# PicTouchTest.net
KiCad netlist of a schematic drawn in EAGLE
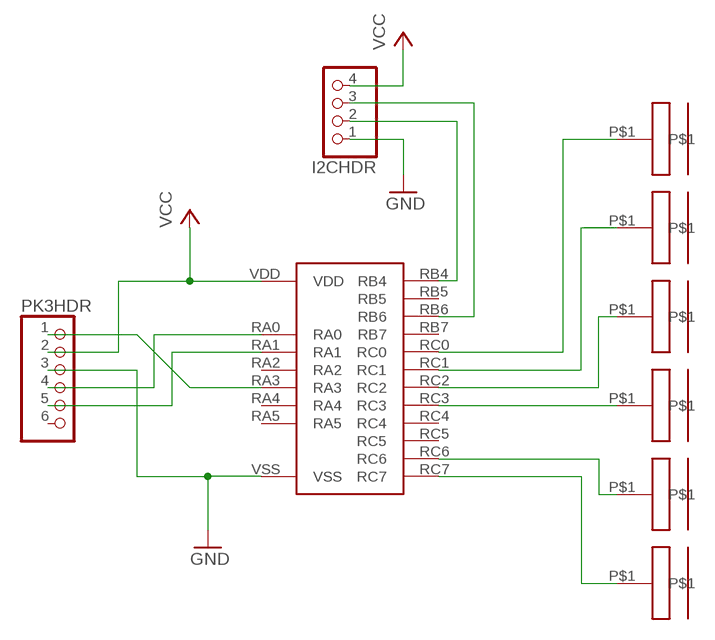
[diagram p0: schematic, sheet 1]

(export (version "E")
  (design (tool "Eeschema 10.0.6"))
  (components
    (comp (ref "I2CHDR")
      (value "PINHD-1X4")
      (footprint "eagle-import:1X04")
      (libsource (lib "eagle-import") (part "PINHD-1X4"))
    )
    (comp (ref "PK3HDR")
      (value "PINHD-1X6")
      (footprint "eagle-import:1X06")
      (libsource (lib "eagle-import") (part "PINHD-1X6"))
    )
    (comp (ref "U$1")
      (value "PIC16F1707")
      (footprint "eagle-import:PIC16F1707")
      (libsource (lib "eagle-import") (part "PIC16F1707"))
    )
    (comp (ref "U$2")
      (value "CAPTOUCH20MMRND")
      (footprint "eagle-import:20MMROUND")
      (libsource (lib "eagle-import") (part "CAPTOUCH20MMRND"))
    )
    (comp (ref "U$3")
      (value "CAPTOUCH20MMRND")
      (footprint "eagle-import:20MMROUND")
      (libsource (lib "eagle-import") (part "CAPTOUCH20MMRND"))
    )
    (comp (ref "U$4")
      (value "CAPTOUCH20MMRND")
      (footprint "eagle-import:20MMROUND")
      (libsource (lib "eagle-import") (part "CAPTOUCH20MMRND"))
    )
    (comp (ref "U$5")
      (value "CAPTOUCH20MMRND")
      (footprint "eagle-import:20MMROUND")
      (libsource (lib "eagle-import") (part "CAPTOUCH20MMRND"))
    )
    (comp (ref "U$6")
      (value "CAPTOUCH20MMRND")
      (footprint "eagle-import:20MMROUND")
      (libsource (lib "eagle-import") (part "CAPTOUCH20MMRND"))
    )
    (comp (ref "U$7")
      (value "CAPTOUCH20MMRND")
      (footprint "eagle-import:20MMROUND")
      (libsource (lib "eagle-import") (part "CAPTOUCH20MMRND"))
    )
  )
  (nets
    (net (code "1") (name "GND") (class "Default")
      (node (ref "I2CHDR") (pin "1") (pinfunction "1_1") (pintype "passive"))
      (node (ref "PK3HDR") (pin "3") (pinfunction "3_3") (pintype "passive"))
      (node (ref "U$1") (pin "VSS") (pinfunction "VSS_VSS") (pintype "bidirectional"))
    )
    (net (code "2") (name "Net-(I2CHDR-Pad2)") (class "Default")
      (node (ref "I2CHDR") (pin "2") (pinfunction "2_2") (pintype "passive"))
      (node (ref "U$1") (pin "RB4") (pinfunction "RB4_RB4") (pintype "bidirectional"))
    )
    (net (code "3") (name "Net-(I2CHDR-Pad3)") (class "Default")
      (node (ref "I2CHDR") (pin "3") (pinfunction "3_3") (pintype "passive"))
      (node (ref "U$1") (pin "RB6") (pinfunction "RB6_RB6") (pintype "bidirectional"))
    )
    (net (code "4") (name "Net-(PK3HDR-Pad1)") (class "Default")
      (node (ref "PK3HDR") (pin "1") (pinfunction "1_1") (pintype "passive"))
      (node (ref "U$1") (pin "RA3") (pinfunction "RA3_RA3") (pintype "bidirectional"))
    )
    (net (code "5") (name "Net-(PK3HDR-Pad4)") (class "Default")
      (node (ref "PK3HDR") (pin "4") (pinfunction "4_4") (pintype "passive"))
      (node (ref "U$1") (pin "RA0") (pinfunction "RA0_RA0") (pintype "bidirectional"))
    )
    (net (code "6") (name "Net-(PK3HDR-Pad5)") (class "Default")
      (node (ref "PK3HDR") (pin "5") (pinfunction "5_5") (pintype "passive"))
      (node (ref "U$1") (pin "RA1") (pinfunction "RA1_RA1") (pintype "bidirectional"))
    )
    (net (code "7") (name "Net-(U$1-PadRC0)") (class "Default")
      (node (ref "U$1") (pin "RC0") (pinfunction "RC0_RC0") (pintype "bidirectional"))
      (node (ref "U$2") (pin "P$1") (pinfunction "P$1_P$1") (pintype "bidirectional"))
    )
    (net (code "8") (name "Net-(U$1-PadRC1)") (class "Default")
      (node (ref "U$1") (pin "RC1") (pinfunction "RC1_RC1") (pintype "bidirectional"))
      (node (ref "U$3") (pin "P$1") (pinfunction "P$1_P$1") (pintype "bidirectional"))
    )
    (net (code "9") (name "Net-(U$1-PadRC2)") (class "Default")
      (node (ref "U$1") (pin "RC2") (pinfunction "RC2_RC2") (pintype "bidirectional"))
      (node (ref "U$4") (pin "P$1") (pinfunction "P$1_P$1") (pintype "bidirectional"))
    )
    (net (code "10") (name "Net-(U$1-PadRC3)") (class "Default")
      (node (ref "U$1") (pin "RC3") (pinfunction "RC3_RC3") (pintype "bidirectional"))
      (node (ref "U$5") (pin "P$1") (pinfunction "P$1_P$1") (pintype "bidirectional"))
    )
    (net (code "11") (name "Net-(U$1-PadRC6)") (class "Default")
      (node (ref "U$1") (pin "RC6") (pinfunction "RC6_RC6") (pintype "bidirectional"))
      (node (ref "U$6") (pin "P$1") (pinfunction "P$1_P$1") (pintype "bidirectional"))
    )
    (net (code "12") (name "Net-(U$1-PadRC7)") (class "Default")
      (node (ref "U$1") (pin "RC7") (pinfunction "RC7_RC7") (pintype "bidirectional"))
      (node (ref "U$7") (pin "P$1") (pinfunction "P$1_P$1") (pintype "bidirectional"))
    )
    (net (code "13") (name "VCC") (class "Default")
      (node (ref "I2CHDR") (pin "4") (pinfunction "4_4") (pintype "passive"))
      (node (ref "PK3HDR") (pin "2") (pinfunction "2_2") (pintype "passive"))
      (node (ref "U$1") (pin "VDD") (pinfunction "VDD_VDD") (pintype "bidirectional"))
    )
    (net (code "14") (name "unconnected-(PK3HDR-Pad6)") (class "Default")
      (node (ref "PK3HDR") (pin "6") (pinfunction "6_6") (pintype "passive"))
    )
    (net (code "15") (name "unconnected-(U$1-PadRA2)") (class "Default")
      (node (ref "U$1") (pin "RA2") (pinfunction "RA2_RA2") (pintype "bidirectional"))
    )
    (net (code "16") (name "unconnected-(U$1-PadRA4)") (class "Default")
      (node (ref "U$1") (pin "RA4") (pinfunction "RA4_RA4") (pintype "bidirectional"))
    )
    (net (code "17") (name "unconnected-(U$1-PadRA5)") (class "Default")
      (node (ref "U$1") (pin "RA5") (pinfunction "RA5_RA5") (pintype "bidirectional"))
    )
    (net (code "18") (name "unconnected-(U$1-PadRB5)") (class "Default")
      (node (ref "U$1") (pin "RB5") (pinfunction "RB5_RB5") (pintype "bidirectional"))
    )
    (net (code "19") (name "unconnected-(U$1-PadRB7)") (class "Default")
      (node (ref "U$1") (pin "RB7") (pinfunction "RB7_RB7") (pintype "bidirectional"))
    )
    (net (code "20") (name "unconnected-(U$1-PadRC4)") (class "Default")
      (node (ref "U$1") (pin "RC4") (pinfunction "RC4_RC4") (pintype "bidirectional"))
    )
    (net (code "21") (name "unconnected-(U$1-PadRC5)") (class "Default")
      (node (ref "U$1") (pin "RC5") (pinfunction "RC5_RC5") (pintype "bidirectional"))
    )
  )
)
